# SmartSwitchBoard1x4vert.net
KiCad netlist of a schematic drawn in EAGLE
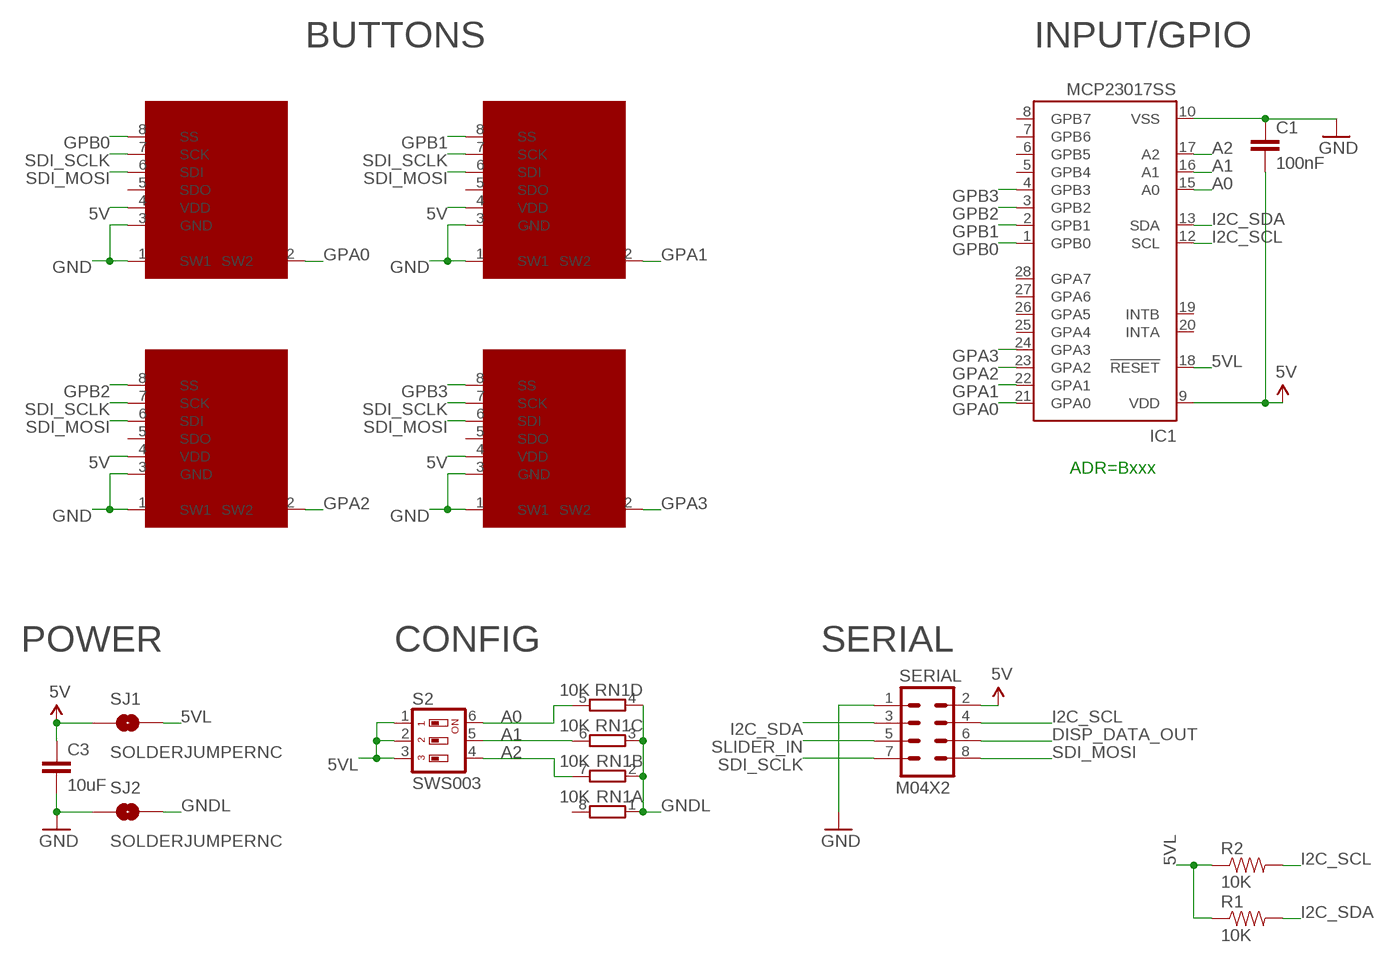
[diagram p0: schematic, sheet 1]

(export (version "E")
  (design (tool "Eeschema 10.0.6"))
  (components
    (comp (ref "C1")
      (value "100nF")
      (footprint "eagle-import:0603-CAP")
      (libsource (lib "eagle-import") (part "CAP0603-CAP"))
    )
    (comp (ref "C3")
      (value "10uF")
      (footprint "eagle-import:0805")
      (libsource (lib "eagle-import") (part "CAP0805"))
    )
    (comp (ref "IC1")
      (value "MCP23017SS")
      (footprint "eagle-import:SSOP28")
      (fields
        (field (name "MF") "MICROCHIP")
        (field (name "MPN") "MCP23017-E/SS")
        (field (name "MPN_1") "MCP23017-E/SS")
        (field (name "OC_FARNELL") "1467674")
        (field (name "OC_NEWARK") "31K2960")
      )
      (libsource (lib "eagle-import") (part "MCP23017SS"))
    )
    (comp (ref "R1")
      (value "10K")
      (footprint "eagle-import:0603-RES")
      (libsource (lib "eagle-import") (part "RESISTOR0603-RES"))
    )
    (comp (ref "R2")
      (value "10K")
      (footprint "eagle-import:0603-RES")
      (libsource (lib "eagle-import") (part "RESISTOR0603-RES"))
    )
    (comp (ref "RN1")
      (value "10K")
      (footprint "eagle-import:CAY16_HAND")
      (libsource (lib "eagle-import") (part "4R-NCAY16"))
    )
    (comp (ref "S2")
      (value "SWS003")
      (footprint "eagle-import:SMS-003")
      (libsource (lib "eagle-import") (part "SWS003"))
    )
    (comp (ref "SERIAL")
      (value "M04X2")
      (footprint "eagle-import:2X4")
      (libsource (lib "eagle-import") (part "M04X2"))
    )
    (comp (ref "SJ1")
      (value "SOLDERJUMPERNC")
      (footprint "eagle-import:SJ_2S")
      (libsource (lib "eagle-import") (part "SOLDERJUMPERNC"))
    )
    (comp (ref "SJ2")
      (value "SOLDERJUMPERNC")
      (footprint "eagle-import:SJ_2S")
      (libsource (lib "eagle-import") (part "SOLDERJUMPERNC"))
    )
    (comp (ref "U$2")
      (value "SMART_SWITCHSMART_SWITCH_8PIN")
      (footprint "eagle-import:SMART_SWITCH")
      (libsource (lib "eagle-import") (part "SMART_SWITCHSMART_SWITCH_8PIN"))
    )
    (comp (ref "U$3")
      (value "SMART_SWITCHSMART_SWITCH_8PIN")
      (footprint "eagle-import:SMART_SWITCH")
      (libsource (lib "eagle-import") (part "SMART_SWITCHSMART_SWITCH_8PIN"))
    )
    (comp (ref "U$4")
      (value "SMART_SWITCHSMART_SWITCH_8PIN")
      (footprint "eagle-import:SMART_SWITCH")
      (libsource (lib "eagle-import") (part "SMART_SWITCHSMART_SWITCH_8PIN"))
    )
    (comp (ref "U$5")
      (value "SMART_SWITCHSMART_SWITCH_8PIN")
      (footprint "eagle-import:SMART_SWITCH")
      (libsource (lib "eagle-import") (part "SMART_SWITCHSMART_SWITCH_8PIN"))
    )
  )
  (nets
    (net (code "1") (name "/5VL") (class "Default")
      (node (ref "IC1") (pin "18") (pinfunction "~{RESET}_18") (pintype "input"))
      (node (ref "R1") (pin "1") (pinfunction "1_1") (pintype "passive"))
      (node (ref "R2") (pin "1") (pinfunction "1_1") (pintype "passive"))
      (node (ref "S2") (pin "1") (pinfunction "1_1") (pintype "passive"))
      (node (ref "S2") (pin "2") (pinfunction "2_2") (pintype "passive"))
      (node (ref "S2") (pin "3") (pinfunction "3_3") (pintype "passive"))
      (node (ref "SJ1") (pin "2") (pinfunction "2_2") (pintype "passive"))
    )
    (net (code "2") (name "/A0") (class "Default")
      (node (ref "IC1") (pin "15") (pinfunction "A0_15") (pintype "input"))
      (node (ref "RN1") (pin "5") (pinfunction "2_5") (pintype "passive"))
      (node (ref "S2") (pin "6") (pinfunction "6_6") (pintype "passive"))
    )
    (net (code "3") (name "/A1") (class "Default")
      (node (ref "IC1") (pin "16") (pinfunction "A1_16") (pintype "input"))
      (node (ref "RN1") (pin "6") (pinfunction "2_6") (pintype "passive"))
      (node (ref "S2") (pin "5") (pinfunction "5_5") (pintype "passive"))
    )
    (net (code "4") (name "/A2") (class "Default")
      (node (ref "IC1") (pin "17") (pinfunction "A2_17") (pintype "input"))
      (node (ref "RN1") (pin "7") (pinfunction "2_7") (pintype "passive"))
      (node (ref "S2") (pin "4") (pinfunction "4_4") (pintype "passive"))
    )
    (net (code "5") (name "/DISP_DATA_OUT") (class "Default")
      (node (ref "SERIAL") (pin "6") (pinfunction "6_6") (pintype "passive"))
    )
    (net (code "6") (name "/GNDL") (class "Default")
      (node (ref "RN1") (pin "1") (pinfunction "1_1") (pintype "passive"))
      (node (ref "RN1") (pin "2") (pinfunction "1_2") (pintype "passive"))
      (node (ref "RN1") (pin "3") (pinfunction "1_3") (pintype "passive"))
      (node (ref "RN1") (pin "4") (pinfunction "1_4") (pintype "passive"))
      (node (ref "SJ2") (pin "2") (pinfunction "2_2") (pintype "passive"))
    )
    (net (code "7") (name "/GPA0") (class "Default")
      (node (ref "IC1") (pin "21") (pinfunction "GPA0_21") (pintype "bidirectional"))
      (node (ref "U$2") (pin "2") (pinfunction "SW2_2") (pintype "bidirectional"))
    )
    (net (code "8") (name "/GPA1") (class "Default")
      (node (ref "IC1") (pin "22") (pinfunction "GPA1_22") (pintype "bidirectional"))
      (node (ref "U$3") (pin "2") (pinfunction "SW2_2") (pintype "bidirectional"))
    )
    (net (code "9") (name "/GPA2") (class "Default")
      (node (ref "IC1") (pin "23") (pinfunction "GPA2_23") (pintype "bidirectional"))
      (node (ref "U$4") (pin "2") (pinfunction "SW2_2") (pintype "bidirectional"))
    )
    (net (code "10") (name "/GPA3") (class "Default")
      (node (ref "IC1") (pin "24") (pinfunction "GPA3_24") (pintype "bidirectional"))
      (node (ref "U$5") (pin "2") (pinfunction "SW2_2") (pintype "bidirectional"))
    )
    (net (code "11") (name "/GPB0") (class "Default")
      (node (ref "IC1") (pin "1") (pinfunction "GPB0_1") (pintype "bidirectional"))
      (node (ref "U$2") (pin "8") (pinfunction "SS_8") (pintype "bidirectional"))
    )
    (net (code "12") (name "/GPB1") (class "Default")
      (node (ref "IC1") (pin "2") (pinfunction "GPB1_2") (pintype "bidirectional"))
      (node (ref "U$3") (pin "8") (pinfunction "SS_8") (pintype "bidirectional"))
    )
    (net (code "13") (name "/GPB2") (class "Default")
      (node (ref "IC1") (pin "3") (pinfunction "GPB2_3") (pintype "bidirectional"))
      (node (ref "U$4") (pin "8") (pinfunction "SS_8") (pintype "bidirectional"))
    )
    (net (code "14") (name "/GPB3") (class "Default")
      (node (ref "IC1") (pin "4") (pinfunction "GPB3_4") (pintype "bidirectional"))
      (node (ref "U$5") (pin "8") (pinfunction "SS_8") (pintype "bidirectional"))
    )
    (net (code "15") (name "/I2C_SCL") (class "Default")
      (node (ref "IC1") (pin "12") (pinfunction "SCL_12") (pintype "input"))
      (node (ref "R2") (pin "2") (pinfunction "2_2") (pintype "passive"))
      (node (ref "SERIAL") (pin "4") (pinfunction "4_4") (pintype "passive"))
    )
    (net (code "16") (name "/I2C_SDA") (class "Default")
      (node (ref "IC1") (pin "13") (pinfunction "SDA_13") (pintype "bidirectional"))
      (node (ref "R1") (pin "2") (pinfunction "2_2") (pintype "passive"))
      (node (ref "SERIAL") (pin "3") (pinfunction "3_3") (pintype "passive"))
    )
    (net (code "17") (name "/SDI_MOSI") (class "Default")
      (node (ref "SERIAL") (pin "8") (pinfunction "8_8") (pintype "passive"))
      (node (ref "U$2") (pin "6") (pinfunction "SDI_6") (pintype "bidirectional"))
      (node (ref "U$3") (pin "6") (pinfunction "SDI_6") (pintype "bidirectional"))
      (node (ref "U$4") (pin "6") (pinfunction "SDI_6") (pintype "bidirectional"))
      (node (ref "U$5") (pin "6") (pinfunction "SDI_6") (pintype "bidirectional"))
    )
    (net (code "18") (name "/SDI_SCLK") (class "Default")
      (node (ref "SERIAL") (pin "7") (pinfunction "7_7") (pintype "passive"))
      (node (ref "U$2") (pin "7") (pinfunction "SCK_7") (pintype "bidirectional"))
      (node (ref "U$3") (pin "7") (pinfunction "SCK_7") (pintype "bidirectional"))
      (node (ref "U$4") (pin "7") (pinfunction "SCK_7") (pintype "bidirectional"))
      (node (ref "U$5") (pin "7") (pinfunction "SCK_7") (pintype "bidirectional"))
    )
    (net (code "19") (name "/SLIDER_IN") (class "Default")
      (node (ref "SERIAL") (pin "5") (pinfunction "5_5") (pintype "passive"))
    )
    (net (code "20") (name "5V") (class "Default")
      (node (ref "C1") (pin "2") (pinfunction "2_2") (pintype "passive"))
      (node (ref "C3") (pin "1") (pinfunction "1_1") (pintype "passive"))
      (node (ref "IC1") (pin "9") (pinfunction "VDD_9") (pintype "power_in"))
      (node (ref "SERIAL") (pin "2") (pinfunction "2_2") (pintype "passive"))
      (node (ref "SJ1") (pin "1") (pinfunction "1_1") (pintype "passive"))
      (node (ref "U$2") (pin "4") (pinfunction "VDD_4") (pintype "bidirectional"))
      (node (ref "U$3") (pin "4") (pinfunction "VDD_4") (pintype "bidirectional"))
      (node (ref "U$4") (pin "4") (pinfunction "VDD_4") (pintype "bidirectional"))
      (node (ref "U$5") (pin "4") (pinfunction "VDD_4") (pintype "bidirectional"))
    )
    (net (code "21") (name "GND") (class "Default")
      (node (ref "C1") (pin "1") (pinfunction "1_1") (pintype "passive"))
      (node (ref "C3") (pin "2") (pinfunction "2_2") (pintype "passive"))
      (node (ref "IC1") (pin "10") (pinfunction "VSS_10") (pintype "power_in"))
      (node (ref "SERIAL") (pin "1") (pinfunction "1_1") (pintype "passive"))
      (node (ref "SJ2") (pin "1") (pinfunction "1_1") (pintype "passive"))
      (node (ref "U$2") (pin "1") (pinfunction "SW1_1") (pintype "bidirectional"))
      (node (ref "U$2") (pin "3") (pinfunction "GND_3") (pintype "bidirectional"))
      (node (ref "U$3") (pin "1") (pinfunction "SW1_1") (pintype "bidirectional"))
      (node (ref "U$3") (pin "3") (pinfunction "GND_3") (pintype "bidirectional"))
      (node (ref "U$4") (pin "1") (pinfunction "SW1_1") (pintype "bidirectional"))
      (node (ref "U$4") (pin "3") (pinfunction "GND_3") (pintype "bidirectional"))
      (node (ref "U$5") (pin "1") (pinfunction "SW1_1") (pintype "bidirectional"))
      (node (ref "U$5") (pin "3") (pinfunction "GND_3") (pintype "bidirectional"))
    )
    (net (code "22") (name "unconnected-(IC1-GPA4-Pad25)") (class "Default")
      (node (ref "IC1") (pin "25") (pinfunction "GPA4_25") (pintype "bidirectional"))
    )
    (net (code "23") (name "unconnected-(IC1-GPA5-Pad26)") (class "Default")
      (node (ref "IC1") (pin "26") (pinfunction "GPA5_26") (pintype "bidirectional"))
    )
    (net (code "24") (name "unconnected-(IC1-GPA6-Pad27)") (class "Default")
      (node (ref "IC1") (pin "27") (pinfunction "GPA6_27") (pintype "bidirectional"))
    )
    (net (code "25") (name "unconnected-(IC1-GPA7-Pad28)") (class "Default")
      (node (ref "IC1") (pin "28") (pinfunction "GPA7_28") (pintype "bidirectional"))
    )
    (net (code "26") (name "unconnected-(IC1-GPB4-Pad5)") (class "Default")
      (node (ref "IC1") (pin "5") (pinfunction "GPB4_5") (pintype "bidirectional"))
    )
    (net (code "27") (name "unconnected-(IC1-GPB5-Pad6)") (class "Default")
      (node (ref "IC1") (pin "6") (pinfunction "GPB5_6") (pintype "bidirectional"))
    )
    (net (code "28") (name "unconnected-(IC1-GPB6-Pad7)") (class "Default")
      (node (ref "IC1") (pin "7") (pinfunction "GPB6_7") (pintype "bidirectional"))
    )
    (net (code "29") (name "unconnected-(IC1-GPB7-Pad8)") (class "Default")
      (node (ref "IC1") (pin "8") (pinfunction "GPB7_8") (pintype "bidirectional"))
    )
    (net (code "30") (name "unconnected-(IC1-INTA-Pad20)") (class "Default")
      (node (ref "IC1") (pin "20") (pinfunction "INTA_20") (pintype "output"))
    )
    (net (code "31") (name "unconnected-(IC1-INTB-Pad19)") (class "Default")
      (node (ref "IC1") (pin "19") (pinfunction "INTB_19") (pintype "output"))
    )
    (net (code "32") (name "unconnected-(RN1A-2-Pad8)") (class "Default")
      (node (ref "RN1") (pin "8") (pinfunction "2_8") (pintype "passive"))
    )
    (net (code "33") (name "unconnected-(U$2-SDO-Pad5)") (class "Default")
      (node (ref "U$2") (pin "5") (pinfunction "SDO_5") (pintype "bidirectional"))
    )
    (net (code "34") (name "unconnected-(U$3-SDO-Pad5)") (class "Default")
      (node (ref "U$3") (pin "5") (pinfunction "SDO_5") (pintype "bidirectional"))
    )
    (net (code "35") (name "unconnected-(U$4-SDO-Pad5)") (class "Default")
      (node (ref "U$4") (pin "5") (pinfunction "SDO_5") (pintype "bidirectional"))
    )
    (net (code "36") (name "unconnected-(U$5-SDO-Pad5)") (class "Default")
      (node (ref "U$5") (pin "5") (pinfunction "SDO_5") (pintype "bidirectional"))
    )
  )
)
